# power.net
KiCad netlist of a schematic drawn in Altium Designer
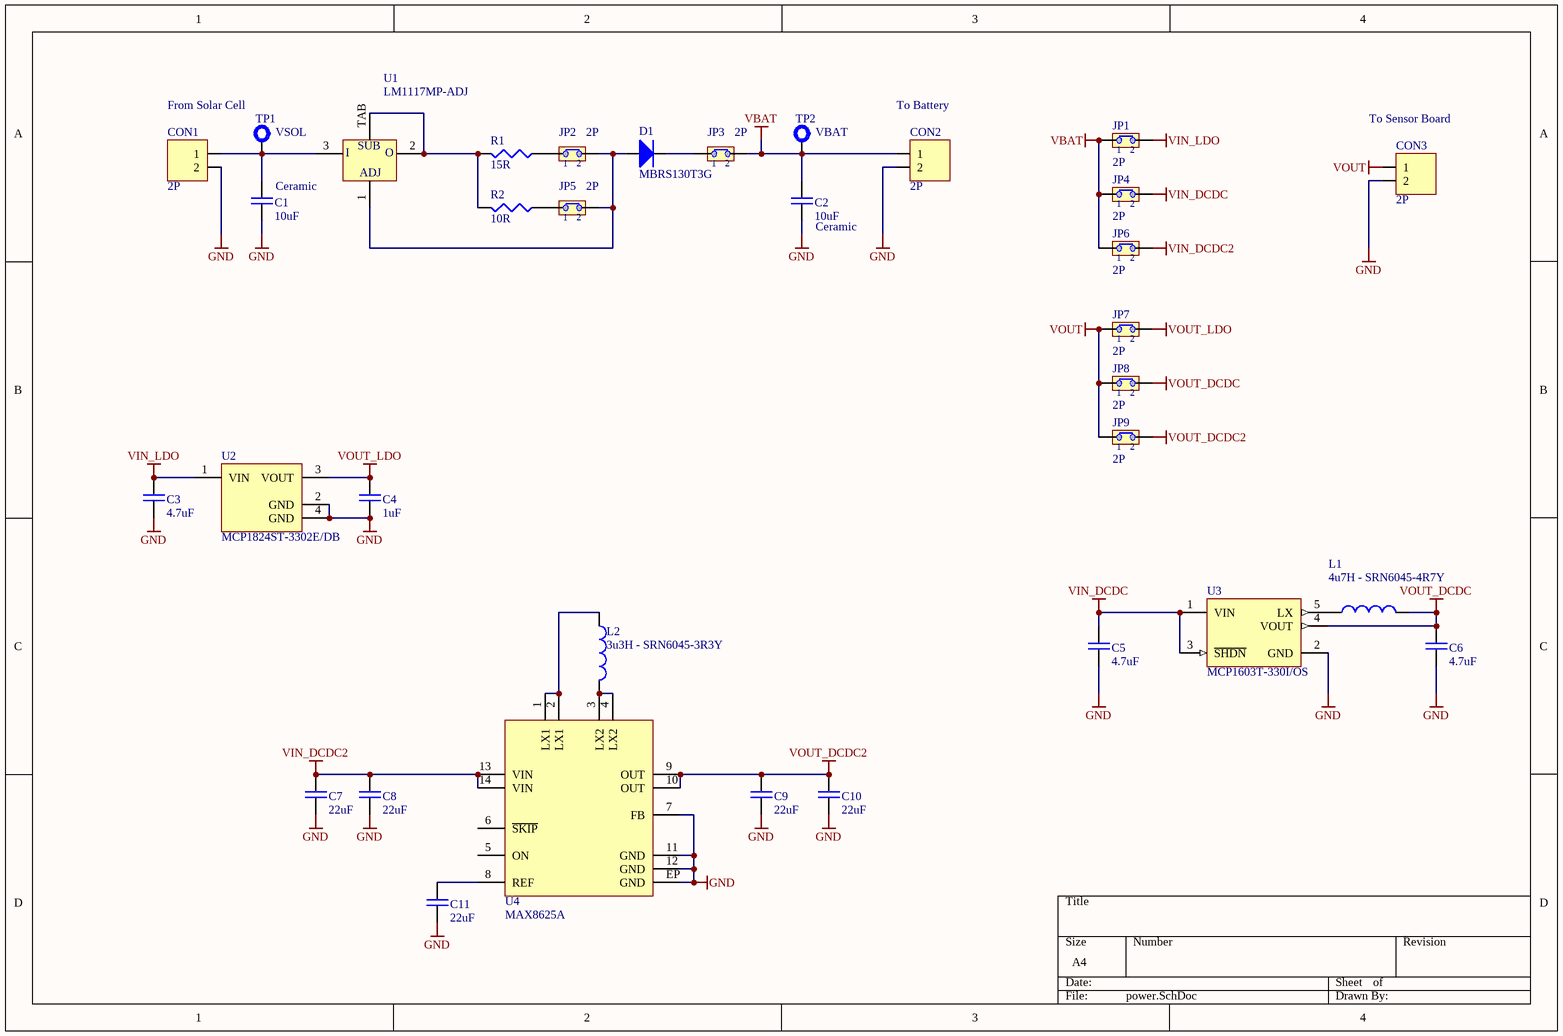
[diagram p0: power.SchDoc]

(export (version "E")
  (design (tool "Eeschema 10.0.6"))
  (components
    (comp (ref "C1")
      (value "10uF")
      (footprint "0805")
      (description "Capacitor")
      (fields (field (name "OWNER") "Nuno Brum"))
      (libsource (lib "Alcetronics_Devices") (part "CAP"))
    )
    (comp (ref "C2")
      (value "10uF")
      (footprint "0805")
      (description "Capacitor")
      (fields (field (name "OWNER") "Nuno Brum"))
      (libsource (lib "Alcetronics_Devices") (part "CAP"))
    )
    (comp (ref "C3")
      (value "4.7uF")
      (footprint "0805")
      (description "Capacitor")
      (fields (field (name "OWNER") "Nuno Brum"))
      (libsource (lib "Alcetronics_Devices") (part "CAP"))
    )
    (comp (ref "C4")
      (value "1uF")
      (footprint "0805")
      (description "Capacitor")
      (fields (field (name "OWNER") "Nuno Brum"))
      (libsource (lib "Alcetronics_Devices") (part "CAP"))
    )
    (comp (ref "C5")
      (value "4.7uF")
      (footprint "0805")
      (description "Capacitor")
      (fields (field (name "OWNER") "Nuno Brum"))
      (libsource (lib "Alcetronics_Devices") (part "CAP"))
    )
    (comp (ref "C6")
      (value "4.7uF")
      (footprint "0805")
      (description "Capacitor")
      (fields (field (name "OWNER") "Nuno Brum"))
      (libsource (lib "Alcetronics_Devices") (part "CAP"))
    )
    (comp (ref "C7")
      (value "22uF")
      (footprint "0805")
      (description "Capacitor")
      (fields (field (name "OWNER") "Nuno Brum"))
      (libsource (lib "Alcetronics_Devices") (part "CAP"))
    )
    (comp (ref "C8")
      (value "22uF")
      (footprint "0805")
      (description "Capacitor")
      (fields (field (name "OWNER") "Nuno Brum"))
      (libsource (lib "Alcetronics_Devices") (part "CAP"))
    )
    (comp (ref "C9")
      (value "22uF")
      (footprint "0805")
      (description "Capacitor")
      (fields (field (name "OWNER") "Nuno Brum"))
      (libsource (lib "Alcetronics_Devices") (part "CAP"))
    )
    (comp (ref "C10")
      (value "22uF")
      (footprint "0805")
      (description "Capacitor")
      (fields (field (name "OWNER") "Nuno Brum"))
      (libsource (lib "Alcetronics_Devices") (part "CAP"))
    )
    (comp (ref "C11")
      (value "22uF")
      (footprint "0805")
      (description "Capacitor")
      (fields (field (name "OWNER") "Nuno Brum"))
      (libsource (lib "Alcetronics_Devices") (part "CAP"))
    )
    (comp (ref "CON1")
      (value "2P")
      (footprint "JST-2MM")
      (description "Connector 2 pins")
      (fields (field (name "OWNER") "Rui Rebelo"))
      (libsource (lib "") (part "CON02_1"))
    )
    (comp (ref "CON2")
      (value "2P")
      (footprint "INTERLOCK2-5MM")
      (description "Connector 2 pins")
      (fields (field (name "OWNER") "Rui Rebelo"))
      (libsource (lib "Alcetronics_EM") (part "CON02"))
    )
    (comp (ref "CON3")
      (value "2P")
      (footprint "INTERLOCK2-5MM")
      (description "Connector 2 pins")
      (fields (field (name "OWNER") "Rui Rebelo"))
      (libsource (lib "Alcetronics_EM") (part "CON02"))
    )
    (comp (ref "D1")
      (value "MBRS130T3G")
      (footprint "DO-214AC")
      (description "Vishay Standard Avalanche Sinterglass Diode")
      (fields (field (name "OWNER") "Nuno Brum"))
      (libsource (lib "CI_Devices") (part "Diode"))
    )
    (comp (ref "JP1")
      (value "2P")
      (footprint "SIP-2")
      (description "2-pin Jumper")
      (fields (field (name "OWNER") "Nuno Brum"))
      (libsource (lib "Alcetronics_EM") (part "JMP2"))
    )
    (comp (ref "JP2")
      (value "2P")
      (footprint "SIP-2")
      (description "2-pin Jumper")
      (fields (field (name "OWNER") "Nuno Brum"))
      (libsource (lib "Alcetronics_EM") (part "JMP2"))
    )
    (comp (ref "JP3")
      (value "2P")
      (footprint "SIP-2")
      (description "2-pin Jumper")
      (fields (field (name "OWNER") "Nuno Brum"))
      (libsource (lib "Alcetronics_EM") (part "JMP2"))
    )
    (comp (ref "JP4")
      (value "2P")
      (footprint "SIP-2")
      (description "2-pin Jumper")
      (fields (field (name "OWNER") "Nuno Brum"))
      (libsource (lib "Alcetronics_EM") (part "JMP2"))
    )
    (comp (ref "JP5")
      (value "2P")
      (footprint "SIP-2")
      (description "2-pin Jumper")
      (fields (field (name "OWNER") "Nuno Brum"))
      (libsource (lib "Alcetronics_EM") (part "JMP2"))
    )
    (comp (ref "JP6")
      (value "2P")
      (footprint "SIP-2")
      (description "2-pin Jumper")
      (fields (field (name "OWNER") "Nuno Brum"))
      (libsource (lib "Alcetronics_EM") (part "JMP2"))
    )
    (comp (ref "JP7")
      (value "2P")
      (footprint "SIP-2")
      (description "2-pin Jumper")
      (fields (field (name "OWNER") "Nuno Brum"))
      (libsource (lib "Alcetronics_EM") (part "JMP2"))
    )
    (comp (ref "JP8")
      (value "2P")
      (footprint "SIP-2")
      (description "2-pin Jumper")
      (fields (field (name "OWNER") "Nuno Brum"))
      (libsource (lib "Alcetronics_EM") (part "JMP2"))
    )
    (comp (ref "JP9")
      (value "2P")
      (footprint "SIP-2")
      (description "2-pin Jumper")
      (fields (field (name "OWNER") "Nuno Brum"))
      (libsource (lib "Alcetronics_EM") (part "JMP2"))
    )
    (comp (ref "L1")
      (value "4u7H - SRN6045-4R7Y")
      (footprint "6X6")
      (description "Inductor")
      (fields (field (name "OWNER") "Nuno Brum"))
      (libsource (lib "Alcetronics_Devices") (part "IND"))
    )
    (comp (ref "L2")
      (value "3u3H - SRN6045-3R3Y")
      (footprint "6X6")
      (description "Inductor")
      (fields (field (name "OWNER") "Nuno Brum"))
      (libsource (lib "Alcetronics_Devices") (part "IND"))
    )
    (comp (ref "R1")
      (value "15R")
      (footprint "0805")
      (description "Resistor")
      (fields (field (name "OWNER") "Nuno Brum"))
      (libsource (lib "Alcetronics_Devices") (part "RES"))
    )
    (comp (ref "R2")
      (value "10R")
      (footprint "0805")
      (description "Resistor")
      (fields (field (name "OWNER") "Nuno Brum"))
      (libsource (lib "Alcetronics_Devices") (part "RES"))
    )
    (comp (ref "TP1")
      (value "VSOL")
      (footprint "TERMINAL")
      (description "Test/Probe Point")
      (fields (field (name "OWNER") "Nuno Brum"))
      (libsource (lib "Alcetronics_EM") (part "TEST-PROBE"))
    )
    (comp (ref "TP2")
      (value "VBAT")
      (footprint "TERMINAL")
      (description "Test/Probe Point")
      (fields (field (name "OWNER") "Nuno Brum"))
      (libsource (lib "Alcetronics_EM") (part "TEST-PROBE"))
    )
    (comp (ref "U1")
      (value "LM1117MP-ADJ")
      (footprint "SOT-223")
      (description "800mA, Low Drop Adjustable Voltage Regulator")
      (fields (field (name "OWNER") "Nuno Brum"))
      (libsource (lib "CI_IC") (part "LM1117-ADJ"))
    )
    (comp (ref "U2")
      (value "MCP1824ST-3302E/DB")
      (footprint "SOT-223-DB3_M")
      (fields (field (name "PUBLISHER") "Altium Limited"))
      (libsource (lib "Microchip Power Mgt Line Regulator") (part "MCP1824ST-3302E/DB"))
    )
    (comp (ref "U3")
      (value "MCP1603T-330I/OS")
      (footprint "TSOT-OS5_M")
      (description "500mA Synchronous Buck Regulator, 3.3V, 2.0 MHz, 5-Pin TSOT, Industrial Temperature, Tape and Reel")
      (fields (field (name "PUBLISHER") "Altium Limited"))
      (libsource (lib "Microchip Power Mgt Switching Regulator") (part "MCP1603T-330I/OS"))
    )
    (comp (ref "U4")
      (value "MAX8625A")
      (footprint "TDFN-EP-14")
      (description "Step up/down DCDC converter")
      (libsource (lib "Alcetronics_IC") (part "MAX8625A"))
    )
  )
  (nets
    (net (code "1") (name "GND") (class "Default")
      (node (ref "C1") (pin "1") (pinfunction "1_1") (pintype "passive"))
      (node (ref "C10") (pin "1") (pinfunction "1_1") (pintype "passive"))
      (node (ref "C11") (pin "2") (pinfunction "2_2") (pintype "passive"))
      (node (ref "C2") (pin "1") (pinfunction "1_1") (pintype "passive"))
      (node (ref "C3") (pin "1") (pinfunction "1_1") (pintype "passive"))
      (node (ref "C4") (pin "1") (pinfunction "1_1") (pintype "passive"))
      (node (ref "C5") (pin "1") (pinfunction "1_1") (pintype "passive"))
      (node (ref "C6") (pin "1") (pinfunction "1_1") (pintype "passive"))
      (node (ref "C7") (pin "2") (pinfunction "2_2") (pintype "passive"))
      (node (ref "C8") (pin "2") (pinfunction "2_2") (pintype "passive"))
      (node (ref "C9") (pin "1") (pinfunction "1_1") (pintype "passive"))
      (node (ref "CON1") (pin "2") (pinfunction "2_2") (pintype "passive"))
      (node (ref "CON2") (pin "2") (pinfunction "2_2") (pintype "passive"))
      (node (ref "CON3") (pin "2") (pinfunction "2_2") (pintype "passive"))
      (node (ref "U2") (pin "2") (pinfunction "GND_2") (pintype "power_in"))
      (node (ref "U2") (pin "4") (pinfunction "GND_4") (pintype "power_in"))
      (node (ref "U3") (pin "2") (pinfunction "GND_2") (pintype "power_in"))
      (node (ref "U4") (pin "11") (pinfunction "GND_11") (pintype "passive"))
      (node (ref "U4") (pin "12") (pinfunction "GND_12") (pintype "passive"))
      (node (ref "U4") (pin "7") (pinfunction "FB_7") (pintype "passive"))
      (node (ref "U4") (pin "EP") (pinfunction "GND_EP") (pintype "passive"))
    )
    (net (code "2") (name "Net-(D1-PadK)") (class "Default")
      (node (ref "D1") (pin "K") (pinfunction "K_K") (pintype "passive"))
      (node (ref "JP3") (pin "1") (pinfunction "1_1") (pintype "passive"))
    )
    (net (code "3") (name "Net-(JP2-Pad1)") (class "Default")
      (node (ref "JP2") (pin "1") (pinfunction "1_1") (pintype "passive"))
      (node (ref "R1") (pin "1") (pinfunction "1_1") (pintype "passive"))
    )
    (net (code "4") (name "Net-(JP5-Pad1)") (class "Default")
      (node (ref "JP5") (pin "1") (pinfunction "1_1") (pintype "passive"))
      (node (ref "R2") (pin "1") (pinfunction "1_1") (pintype "passive"))
    )
    (net (code "5") (name "Net-(L2-Pad1)") (class "Default")
      (node (ref "L2") (pin "1") (pinfunction "1_1") (pintype "passive"))
      (node (ref "U4") (pin "1") (pinfunction "LX1_1") (pintype "passive"))
      (node (ref "U4") (pin "2") (pinfunction "LX1_2") (pintype "passive"))
    )
    (net (code "6") (name "Net-(L2-Pad2)") (class "Default")
      (node (ref "L2") (pin "2") (pinfunction "2_2") (pintype "passive"))
      (node (ref "U4") (pin "3") (pinfunction "LX2_3") (pintype "passive"))
      (node (ref "U4") (pin "4") (pinfunction "LX2_4") (pintype "passive"))
    )
    (net (code "7") (name "Net-(TP1-TP)") (class "Default")
      (node (ref "C1") (pin "2") (pinfunction "2_2") (pintype "passive"))
      (node (ref "CON1") (pin "1") (pinfunction "1_1") (pintype "passive"))
      (node (ref "TP1") (pin "1") (pinfunction "TP_1") (pintype "passive"))
      (node (ref "U1") (pin "3") (pinfunction "IN_3") (pintype "power_in"))
    )
    (net (code "8") (name "Net-(U1-ADJ)") (class "Default")
      (node (ref "D1") (pin "A") (pinfunction "A_A") (pintype "passive"))
      (node (ref "JP2") (pin "2") (pinfunction "2_2") (pintype "passive"))
      (node (ref "JP5") (pin "2") (pinfunction "2_2") (pintype "passive"))
      (node (ref "U1") (pin "1") (pinfunction "ADJ_1") (pintype "passive"))
    )
    (net (code "9") (name "Net-(U1-OUT)") (class "Default")
      (node (ref "R1") (pin "2") (pinfunction "2_2") (pintype "passive"))
      (node (ref "R2") (pin "2") (pinfunction "2_2") (pintype "passive"))
      (node (ref "U1") (pin "2") (pinfunction "OUT_2") (pintype "power_in"))
      (node (ref "U1") (pin "TAB") (pinfunction "SUB_TAB") (pintype "power_in"))
    )
    (net (code "10") (name "Net-(U3-LX)") (class "Default")
      (node (ref "L1") (pin "1") (pinfunction "1_1") (pintype "passive"))
      (node (ref "U3") (pin "5") (pinfunction "LX_5") (pintype "output"))
    )
    (net (code "11") (name "Net-(U4-REF)") (class "Default")
      (node (ref "C11") (pin "1") (pinfunction "1_1") (pintype "passive"))
      (node (ref "U4") (pin "8") (pinfunction "REF_8") (pintype "passive"))
    )
    (net (code "12") (name "VBAT") (class "Default")
      (node (ref "C2") (pin "2") (pinfunction "2_2") (pintype "passive"))
      (node (ref "CON2") (pin "1") (pinfunction "1_1") (pintype "passive"))
      (node (ref "JP1") (pin "1") (pinfunction "1_1") (pintype "passive"))
      (node (ref "JP3") (pin "2") (pinfunction "2_2") (pintype "passive"))
      (node (ref "JP4") (pin "1") (pinfunction "1_1") (pintype "passive"))
      (node (ref "JP6") (pin "1") (pinfunction "1_1") (pintype "passive"))
      (node (ref "TP2") (pin "1") (pinfunction "TP_1") (pintype "passive"))
    )
    (net (code "13") (name "VIN_DCDC") (class "Default")
      (node (ref "C5") (pin "2") (pinfunction "2_2") (pintype "passive"))
      (node (ref "JP4") (pin "2") (pinfunction "2_2") (pintype "passive"))
      (node (ref "U3") (pin "1") (pinfunction "VIN_1") (pintype "power_in"))
      (node (ref "U3") (pin "3") (pinfunction "~{SHDN}_3") (pintype "input"))
    )
    (net (code "14") (name "VIN_DCDC2") (class "Default")
      (node (ref "C7") (pin "1") (pinfunction "1_1") (pintype "passive"))
      (node (ref "C8") (pin "1") (pinfunction "1_1") (pintype "passive"))
      (node (ref "JP6") (pin "2") (pinfunction "2_2") (pintype "passive"))
      (node (ref "U4") (pin "13") (pinfunction "VIN_13") (pintype "passive"))
      (node (ref "U4") (pin "14") (pinfunction "VIN_14") (pintype "passive"))
    )
    (net (code "15") (name "VIN_LDO") (class "Default")
      (node (ref "C3") (pin "2") (pinfunction "2_2") (pintype "passive"))
      (node (ref "JP1") (pin "2") (pinfunction "2_2") (pintype "passive"))
      (node (ref "U2") (pin "1") (pinfunction "VIN_1") (pintype "power_in"))
    )
    (net (code "16") (name "VOUT") (class "Default")
      (node (ref "CON3") (pin "1") (pinfunction "1_1") (pintype "passive"))
      (node (ref "JP7") (pin "1") (pinfunction "1_1") (pintype "passive"))
      (node (ref "JP8") (pin "1") (pinfunction "1_1") (pintype "passive"))
      (node (ref "JP9") (pin "1") (pinfunction "1_1") (pintype "passive"))
    )
    (net (code "17") (name "VOUT_DCDC") (class "Default")
      (node (ref "C6") (pin "2") (pinfunction "2_2") (pintype "passive"))
      (node (ref "JP8") (pin "2") (pinfunction "2_2") (pintype "passive"))
      (node (ref "L1") (pin "2") (pinfunction "2_2") (pintype "passive"))
      (node (ref "U3") (pin "4") (pinfunction "VOUT_4") (pintype "output"))
    )
    (net (code "18") (name "VOUT_DCDC2") (class "Default")
      (node (ref "C10") (pin "2") (pinfunction "2_2") (pintype "passive"))
      (node (ref "C9") (pin "2") (pinfunction "2_2") (pintype "passive"))
      (node (ref "JP9") (pin "2") (pinfunction "2_2") (pintype "passive"))
      (node (ref "U4") (pin "10") (pinfunction "OUT_10") (pintype "passive"))
      (node (ref "U4") (pin "9") (pinfunction "OUT_9") (pintype "passive"))
    )
    (net (code "19") (name "VOUT_LDO") (class "Default")
      (node (ref "C4") (pin "2") (pinfunction "2_2") (pintype "passive"))
      (node (ref "JP7") (pin "2") (pinfunction "2_2") (pintype "passive"))
      (node (ref "U2") (pin "3") (pinfunction "VOUT_3") (pintype "power_in"))
    )
    (net (code "20") (name "unconnected-(U4-ON-Pad5)") (class "Default")
      (node (ref "U4") (pin "5") (pinfunction "ON_5") (pintype "passive"))
    )
    (net (code "21") (name "unconnected-(U4-~{SKIP}-Pad6)") (class "Default")
      (node (ref "U4") (pin "6") (pinfunction "~{SKIP}_6") (pintype "passive"))
    )
  )
)
